# 11_-FPGA_Bank_4_Interface.net
KiCad netlist of a schematic drawn in Altium Designer
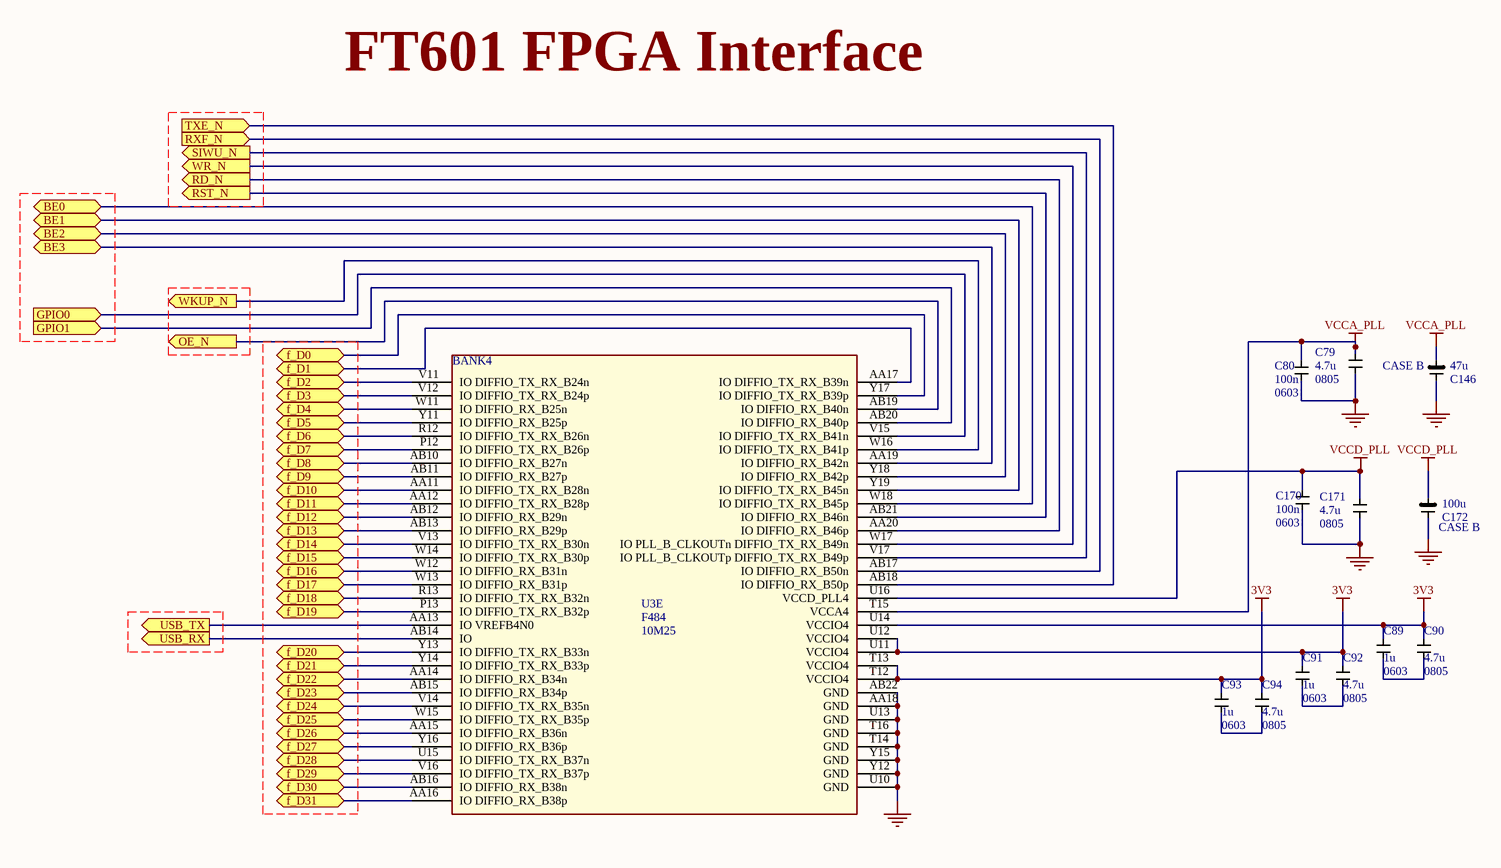
[diagram p0: [11]-FPGA_Bank_4_Interface.SchDoc]

(export (version "E")
  (design (tool "Eeschema 10.0.6"))
  (components
    (comp (ref "C79")
      (value "4.7u")
      (fields (field (name "PCB FOOTPRINT") "0805"))
      (libsource (lib "06031C104KAT2A") (part "Component_1"))
    )
    (comp (ref "C80")
      (value "100n")
      (footprint "*0603")
      (fields (field (name "PCB LAYER:") "0603"))
      (libsource (lib "0603YC105KAT2A") (part "Component_1"))
    )
    (comp (ref "C89")
      (value "1u")
      (footprint "*0603")
      (fields (field (name "PCB LAYER:") "0603"))
      (libsource (lib "0603YC105KAT2A") (part "Component_1"))
    )
    (comp (ref "C90")
      (value "4.7u")
      (footprint "*CAPC2013X140N")
      (fields (field (name "PCB PACKAGE") "0805"))
      (libsource (lib "08053D475KAT2A") (part "Component_1"))
    )
    (comp (ref "C91")
      (value "1u")
      (footprint "*0603")
      (fields (field (name "PCB LAYER:") "0603"))
      (libsource (lib "0603YC105KAT2A") (part "Component_1"))
    )
    (comp (ref "C92")
      (value "4.7u")
      (footprint "*CAPC2013X140N")
      (fields (field (name "PCB PACKAGE") "0805"))
      (libsource (lib "08053D475KAT2A") (part "Component_1"))
    )
    (comp (ref "C93")
      (value "1u")
      (footprint "*0603")
      (fields (field (name "PCB LAYER:") "0603"))
      (libsource (lib "0603YC105KAT2A") (part "Component_1"))
    )
    (comp (ref "C94")
      (value "4.7u")
      (footprint "*CAPC2013X140N")
      (fields (field (name "PCB PACKAGE") "0805"))
      (libsource (lib "08053D475KAT2A") (part "Component_1"))
    )
    (comp (ref "C146")
      (value "47u")
      (footprint "CAPC3529X21N")
      (fields (field (name "CASE") "CASE B"))
      (libsource (lib "TAJB107K006TNJ") (part "Component_1"))
    )
    (comp (ref "C170")
      (value "100n")
      (footprint "*0603")
      (fields (field (name "PCB LAYER:") "0603"))
      (libsource (lib "0603YC105KAT2A") (part "Component_1"))
    )
    (comp (ref "C171")
      (value "4.7u")
      (fields (field (name "PCB FOOTPRINT") "0805"))
      (libsource (lib "06031C104KAT2A") (part "Component_1"))
    )
    (comp (ref "C172")
      (value "100u")
      (footprint "CAPC3529X21N")
      (fields (field (name "CASE") "CASE B"))
      (libsource (lib "TAJB107K006TNJ") (part "Component_1"))
    )
    (comp (ref "U3")
      (value "10M25")
      (footprint "*BGA484C100P22X22_2300X2300X200N")
      (fields (field (name "PART NO.") "10M25DAF484I7G") (field (name "PACKAGE TYPE") "F484"))
      (libsource (lib "10M25DAF484I7G") (part "Component_1"))
    )
  )
  (nets
    (net (code "1") (name "/BE0") (class "Default")
      (node (ref "U3") (pin "W18") (pinfunction "IO_DIFFIO_TX_RX_B45p_W18") (pintype "passive"))
    )
    (net (code "2") (name "/BE1") (class "Default")
      (node (ref "U3") (pin "Y19") (pinfunction "IO_DIFFIO_TX_RX_B45n_Y19") (pintype "passive"))
    )
    (net (code "3") (name "/BE2") (class "Default")
      (node (ref "U3") (pin "Y18") (pinfunction "IO_DIFFIO_RX_B42p_Y18") (pintype "passive"))
    )
    (net (code "4") (name "/BE3") (class "Default")
      (node (ref "U3") (pin "AA19") (pinfunction "IO_DIFFIO_RX_B42n_AA19") (pintype "passive"))
    )
    (net (code "5") (name "/GPIO0") (class "Default")
      (node (ref "U3") (pin "V15") (pinfunction "IO_DIFFIO_TX_RX_B41n_V15") (pintype "passive"))
    )
    (net (code "6") (name "/GPIO1") (class "Default")
      (node (ref "U3") (pin "AB20") (pinfunction "IO_DIFFIO_RX_B40p_AB20") (pintype "passive"))
    )
    (net (code "7") (name "/OE_N") (class "Default")
      (node (ref "U3") (pin "AB19") (pinfunction "IO_DIFFIO_RX_B40n_AB19") (pintype "passive"))
    )
    (net (code "8") (name "/RD_N") (class "Default")
      (node (ref "U3") (pin "AA20") (pinfunction "IO_DIFFIO_RX_B46p_AA20") (pintype "passive"))
    )
    (net (code "9") (name "/RST_N") (class "Default")
      (node (ref "U3") (pin "AB21") (pinfunction "IO_DIFFIO_RX_B46n_AB21") (pintype "passive"))
    )
    (net (code "10") (name "/RXF_N") (class "Default")
      (node (ref "U3") (pin "AB17") (pinfunction "IO_DIFFIO_RX_B50n_AB17") (pintype "passive"))
    )
    (net (code "11") (name "/SIWU_N") (class "Default")
      (node (ref "U3") (pin "V17") (pinfunction "IO_PLL_B_CLKOUTp_DIFFIO_TX_RX_B49p_V17") (pintype "passive"))
    )
    (net (code "12") (name "/TXE_N") (class "Default")
      (node (ref "U3") (pin "AB18") (pinfunction "IO_DIFFIO_RX_B50p_AB18") (pintype "passive"))
    )
    (net (code "13") (name "/USB_RX") (class "Default")
      (node (ref "U3") (pin "AB14") (pinfunction "IO_AB14") (pintype "passive"))
    )
    (net (code "14") (name "/USB_TX") (class "Default")
      (node (ref "U3") (pin "AA13") (pinfunction "IO_VREFB4N0_AA13") (pintype "passive"))
    )
    (net (code "15") (name "/WKUP_N") (class "Default")
      (node (ref "U3") (pin "W16") (pinfunction "IO_DIFFIO_TX_RX_B41p_W16") (pintype "passive"))
    )
    (net (code "16") (name "/WR_N") (class "Default")
      (node (ref "U3") (pin "W17") (pinfunction "IO_PLL_B_CLKOUTn_DIFFIO_TX_RX_B49n_W17") (pintype "passive"))
    )
    (net (code "17") (name "/f_D0") (class "Default")
      (node (ref "U3") (pin "Y17") (pinfunction "IO_DIFFIO_TX_RX_B39p_Y17") (pintype "passive"))
    )
    (net (code "18") (name "/f_D1") (class "Default")
      (node (ref "U3") (pin "AA17") (pinfunction "IO_DIFFIO_TX_RX_B39n_AA17") (pintype "passive"))
    )
    (net (code "19") (name "/f_D2") (class "Default")
      (node (ref "U3") (pin "V11") (pinfunction "IO_DIFFIO_TX_RX_B24n_V11") (pintype "passive"))
    )
    (net (code "20") (name "/f_D3") (class "Default")
      (node (ref "U3") (pin "V12") (pinfunction "IO_DIFFIO_TX_RX_B24p_V12") (pintype "passive"))
    )
    (net (code "21") (name "/f_D4") (class "Default")
      (node (ref "U3") (pin "W11") (pinfunction "IO_DIFFIO_RX_B25n_W11") (pintype "passive"))
    )
    (net (code "22") (name "/f_D5") (class "Default")
      (node (ref "U3") (pin "Y11") (pinfunction "IO_DIFFIO_RX_B25p_Y11") (pintype "passive"))
    )
    (net (code "23") (name "/f_D6") (class "Default")
      (node (ref "U3") (pin "R12") (pinfunction "IO_DIFFIO_TX_RX_B26n_R12") (pintype "passive"))
    )
    (net (code "24") (name "/f_D7") (class "Default")
      (node (ref "U3") (pin "P12") (pinfunction "IO_DIFFIO_TX_RX_B26p_P12") (pintype "passive"))
    )
    (net (code "25") (name "/f_D8") (class "Default")
      (node (ref "U3") (pin "AB10") (pinfunction "IO_DIFFIO_RX_B27n_AB10") (pintype "passive"))
    )
    (net (code "26") (name "/f_D9") (class "Default")
      (node (ref "U3") (pin "AB11") (pinfunction "IO_DIFFIO_RX_B27p_AB11") (pintype "passive"))
    )
    (net (code "27") (name "/f_D10") (class "Default")
      (node (ref "U3") (pin "AA11") (pinfunction "IO_DIFFIO_TX_RX_B28n_AA11") (pintype "passive"))
    )
    (net (code "28") (name "/f_D11") (class "Default")
      (node (ref "U3") (pin "AA12") (pinfunction "IO_DIFFIO_TX_RX_B28p_AA12") (pintype "passive"))
    )
    (net (code "29") (name "/f_D12") (class "Default")
      (node (ref "U3") (pin "AB12") (pinfunction "IO_DIFFIO_RX_B29n_AB12") (pintype "passive"))
    )
    (net (code "30") (name "/f_D13") (class "Default")
      (node (ref "U3") (pin "AB13") (pinfunction "IO_DIFFIO_RX_B29p_AB13") (pintype "passive"))
    )
    (net (code "31") (name "/f_D14") (class "Default")
      (node (ref "U3") (pin "V13") (pinfunction "IO_DIFFIO_TX_RX_B30n_V13") (pintype "passive"))
    )
    (net (code "32") (name "/f_D15") (class "Default")
      (node (ref "U3") (pin "W14") (pinfunction "IO_DIFFIO_TX_RX_B30p_W14") (pintype "passive"))
    )
    (net (code "33") (name "/f_D16") (class "Default")
      (node (ref "U3") (pin "W12") (pinfunction "IO_DIFFIO_RX_B31n_W12") (pintype "passive"))
    )
    (net (code "34") (name "/f_D17") (class "Default")
      (node (ref "U3") (pin "W13") (pinfunction "IO_DIFFIO_RX_B31p_W13") (pintype "passive"))
    )
    (net (code "35") (name "/f_D18") (class "Default")
      (node (ref "U3") (pin "R13") (pinfunction "IO_DIFFIO_TX_RX_B32n_R13") (pintype "passive"))
    )
    (net (code "36") (name "/f_D19") (class "Default")
      (node (ref "U3") (pin "P13") (pinfunction "IO_DIFFIO_TX_RX_B32p_P13") (pintype "passive"))
    )
    (net (code "37") (name "/f_D20") (class "Default")
      (node (ref "U3") (pin "Y13") (pinfunction "IO_DIFFIO_TX_RX_B33n_Y13") (pintype "passive"))
    )
    (net (code "38") (name "/f_D21") (class "Default")
      (node (ref "U3") (pin "Y14") (pinfunction "IO_DIFFIO_TX_RX_B33p_Y14") (pintype "passive"))
    )
    (net (code "39") (name "/f_D22") (class "Default")
      (node (ref "U3") (pin "AA14") (pinfunction "IO_DIFFIO_RX_B34n_AA14") (pintype "passive"))
    )
    (net (code "40") (name "/f_D23") (class "Default")
      (node (ref "U3") (pin "AB15") (pinfunction "IO_DIFFIO_RX_B34p_AB15") (pintype "passive"))
    )
    (net (code "41") (name "/f_D24") (class "Default")
      (node (ref "U3") (pin "V14") (pinfunction "IO_DIFFIO_TX_RX_B35n_V14") (pintype "passive"))
    )
    (net (code "42") (name "/f_D25") (class "Default")
      (node (ref "U3") (pin "W15") (pinfunction "IO_DIFFIO_TX_RX_B35p_W15") (pintype "passive"))
    )
    (net (code "43") (name "/f_D26") (class "Default")
      (node (ref "U3") (pin "AA15") (pinfunction "IO_DIFFIO_RX_B36n_AA15") (pintype "passive"))
    )
    (net (code "44") (name "/f_D27") (class "Default")
      (node (ref "U3") (pin "Y16") (pinfunction "IO_DIFFIO_RX_B36p_Y16") (pintype "passive"))
    )
    (net (code "45") (name "/f_D28") (class "Default")
      (node (ref "U3") (pin "U15") (pinfunction "IO_DIFFIO_TX_RX_B37n_U15") (pintype "passive"))
    )
    (net (code "46") (name "/f_D29") (class "Default")
      (node (ref "U3") (pin "V16") (pinfunction "IO_DIFFIO_TX_RX_B37p_V16") (pintype "passive"))
    )
    (net (code "47") (name "/f_D30") (class "Default")
      (node (ref "U3") (pin "AB16") (pinfunction "IO_DIFFIO_RX_B38n_AB16") (pintype "passive"))
    )
    (net (code "48") (name "/f_D31") (class "Default")
      (node (ref "U3") (pin "AA16") (pinfunction "IO_DIFFIO_RX_B38p_AA16") (pintype "passive"))
    )
    (net (code "49") (name "3V3") (class "Default")
      (node (ref "C89") (pin "2") (pinfunction "2_2") (pintype "passive"))
      (node (ref "C90") (pin "2") (pinfunction "2_2") (pintype "passive"))
      (node (ref "C91") (pin "2") (pinfunction "2_2") (pintype "passive"))
      (node (ref "C92") (pin "2") (pinfunction "2_2") (pintype "passive"))
      (node (ref "C93") (pin "2") (pinfunction "2_2") (pintype "passive"))
      (node (ref "C94") (pin "2") (pinfunction "2_2") (pintype "passive"))
      (node (ref "U3") (pin "T12") (pinfunction "VCCIO4_T12") (pintype "passive"))
      (node (ref "U3") (pin "T13") (pinfunction "VCCIO4_T13") (pintype "passive"))
      (node (ref "U3") (pin "U11") (pinfunction "VCCIO4_U11") (pintype "passive"))
      (node (ref "U3") (pin "U12") (pinfunction "VCCIO4_U12") (pintype "passive"))
      (node (ref "U3") (pin "U14") (pinfunction "VCCIO4_U14") (pintype "passive"))
    )
    (net (code "50") (name "GND") (class "Default")
      (node (ref "C146") (pin "2") (pinfunction "2_2") (pintype "passive"))
      (node (ref "C170") (pin "1") (pinfunction "1_1") (pintype "passive"))
      (node (ref "C171") (pin "1") (pinfunction "1_1") (pintype "passive"))
      (node (ref "C172") (pin "2") (pinfunction "2_2") (pintype "passive"))
      (node (ref "C79") (pin "1") (pinfunction "1_1") (pintype "passive"))
      (node (ref "C80") (pin "1") (pinfunction "1_1") (pintype "passive"))
      (node (ref "U3") (pin "AA18") (pinfunction "GND_AA18") (pintype "passive"))
      (node (ref "U3") (pin "AB22") (pinfunction "GND_AB22") (pintype "passive"))
      (node (ref "U3") (pin "T14") (pinfunction "GND_T14") (pintype "passive"))
      (node (ref "U3") (pin "T16") (pinfunction "GND_T16") (pintype "passive"))
      (node (ref "U3") (pin "U10") (pinfunction "GND_U10") (pintype "passive"))
      (node (ref "U3") (pin "U13") (pinfunction "GND_U13") (pintype "passive"))
      (node (ref "U3") (pin "Y12") (pinfunction "GND_Y12") (pintype "passive"))
      (node (ref "U3") (pin "Y15") (pinfunction "GND_Y15") (pintype "passive"))
    )
    (net (code "51") (name "Net-(C89-Pad1)") (class "Default")
      (node (ref "C89") (pin "1") (pinfunction "1_1") (pintype "passive"))
      (node (ref "C90") (pin "1") (pinfunction "1_1") (pintype "passive"))
    )
    (net (code "52") (name "Net-(C91-Pad1)") (class "Default")
      (node (ref "C91") (pin "1") (pinfunction "1_1") (pintype "passive"))
      (node (ref "C92") (pin "1") (pinfunction "1_1") (pintype "passive"))
    )
    (net (code "53") (name "Net-(C93-Pad1)") (class "Default")
      (node (ref "C93") (pin "1") (pinfunction "1_1") (pintype "passive"))
      (node (ref "C94") (pin "1") (pinfunction "1_1") (pintype "passive"))
    )
    (net (code "54") (name "VCCA_PLL") (class "Default")
      (node (ref "C146") (pin "1") (pinfunction "1_1") (pintype "passive"))
      (node (ref "C79") (pin "2") (pinfunction "2_2") (pintype "passive"))
      (node (ref "C80") (pin "2") (pinfunction "2_2") (pintype "passive"))
      (node (ref "U3") (pin "T15") (pinfunction "VCCA4_T15") (pintype "passive"))
    )
    (net (code "55") (name "VCCD_PLL") (class "Default")
      (node (ref "C170") (pin "2") (pinfunction "2_2") (pintype "passive"))
      (node (ref "C171") (pin "2") (pinfunction "2_2") (pintype "passive"))
      (node (ref "C172") (pin "1") (pinfunction "1_1") (pintype "passive"))
      (node (ref "U3") (pin "U16") (pinfunction "VCCD_PLL4_U16") (pintype "passive"))
    )
  )
)
